# at32uc3a3256_usb_i2s.net
KiCad netlist of a schematic drawn in EAGLE
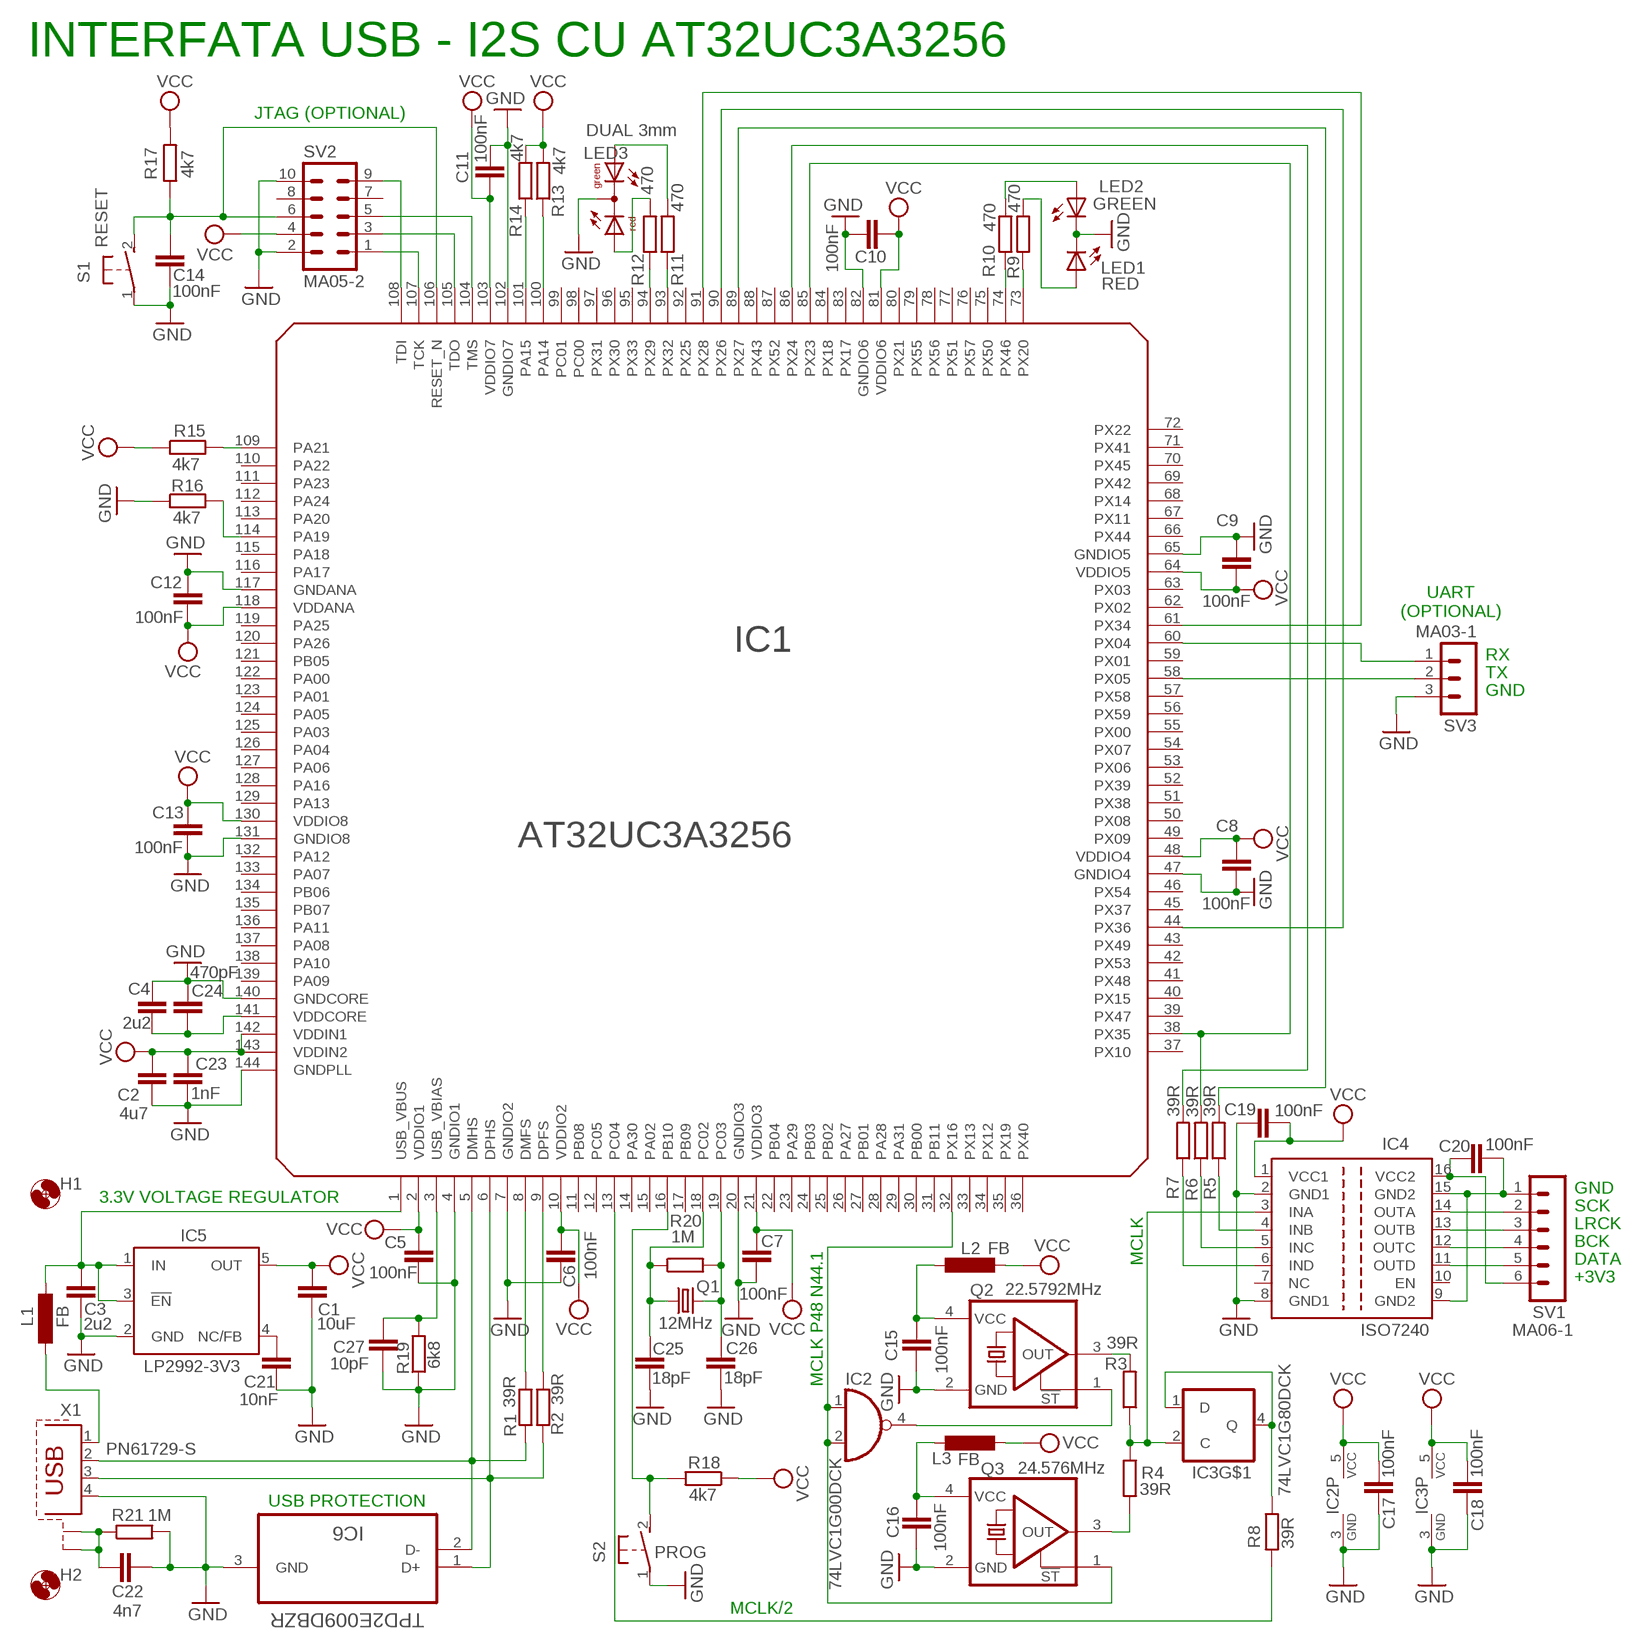
[diagram p0: schematic, sheet 1]

(export (version "E")
  (design (tool "Eeschema 10.0.6"))
  (components
    (comp (ref "C1")
      (value "10uF")
      (footprint "eagle-import:C0603")
      (libsource (lib "eagle-import") (part "C-EUC0603"))
    )
    (comp (ref "C2")
      (value "4u7")
      (footprint "eagle-import:C0603")
      (libsource (lib "eagle-import") (part "C-EUC0603"))
    )
    (comp (ref "C3")
      (value "2u2")
      (footprint "eagle-import:C0603")
      (libsource (lib "eagle-import") (part "C-EUC0603"))
    )
    (comp (ref "C4")
      (value "2u2")
      (footprint "eagle-import:C0603")
      (libsource (lib "eagle-import") (part "C-EUC0603"))
    )
    (comp (ref "C5")
      (value "100nF")
      (footprint "eagle-import:C0603")
      (libsource (lib "eagle-import") (part "C-EUC0603"))
    )
    (comp (ref "C6")
      (value "100nF")
      (footprint "eagle-import:C0603")
      (libsource (lib "eagle-import") (part "C-EUC0603"))
    )
    (comp (ref "C7")
      (value "100nF")
      (footprint "eagle-import:C0603")
      (libsource (lib "eagle-import") (part "C-EUC0603"))
    )
    (comp (ref "C8")
      (value "100nF")
      (footprint "eagle-import:C0603")
      (libsource (lib "eagle-import") (part "C-EUC0603"))
    )
    (comp (ref "C9")
      (value "100nF")
      (footprint "eagle-import:C0603")
      (libsource (lib "eagle-import") (part "C-EUC0603"))
    )
    (comp (ref "C10")
      (value "100nF")
      (footprint "eagle-import:C0603")
      (libsource (lib "eagle-import") (part "C-EUC0603"))
    )
    (comp (ref "C11")
      (value "100nF")
      (footprint "eagle-import:C0603")
      (libsource (lib "eagle-import") (part "C-EUC0603"))
    )
    (comp (ref "C12")
      (value "100nF")
      (footprint "eagle-import:C0603")
      (libsource (lib "eagle-import") (part "C-EUC0603"))
    )
    (comp (ref "C13")
      (value "100nF")
      (footprint "eagle-import:C0603")
      (libsource (lib "eagle-import") (part "C-EUC0603"))
    )
    (comp (ref "C14")
      (value "100nF")
      (footprint "eagle-import:C0603")
      (libsource (lib "eagle-import") (part "C-EUC0603"))
    )
    (comp (ref "C15")
      (value "100nF")
      (footprint "eagle-import:C0603")
      (libsource (lib "eagle-import") (part "C-EUC0603"))
    )
    (comp (ref "C16")
      (value "100nF")
      (footprint "eagle-import:C0603")
      (libsource (lib "eagle-import") (part "C-EUC0603"))
    )
    (comp (ref "C17")
      (value "100nF")
      (footprint "eagle-import:C0603")
      (libsource (lib "eagle-import") (part "C-EUC0603"))
    )
    (comp (ref "C18")
      (value "100nF")
      (footprint "eagle-import:C0603")
      (libsource (lib "eagle-import") (part "C-EUC0603"))
    )
    (comp (ref "C19")
      (value "100nF")
      (footprint "eagle-import:C0603")
      (libsource (lib "eagle-import") (part "C-EUC0603"))
    )
    (comp (ref "C20")
      (value "100nF")
      (footprint "eagle-import:C0603")
      (libsource (lib "eagle-import") (part "C-EUC0603"))
    )
    (comp (ref "C21")
      (value "10nF")
      (footprint "eagle-import:C0603")
      (libsource (lib "eagle-import") (part "C-EUC0603"))
    )
    (comp (ref "C22")
      (value "4n7")
      (footprint "eagle-import:C0603")
      (libsource (lib "eagle-import") (part "C-EUC0603"))
    )
    (comp (ref "C23")
      (value "1nF")
      (footprint "eagle-import:C0603")
      (libsource (lib "eagle-import") (part "C-EUC0603"))
    )
    (comp (ref "C24")
      (value "470pF")
      (footprint "eagle-import:C0603")
      (libsource (lib "eagle-import") (part "C-EUC0603"))
    )
    (comp (ref "C25")
      (value "18pF")
      (footprint "eagle-import:C0603")
      (libsource (lib "eagle-import") (part "C-EUC0603"))
    )
    (comp (ref "C26")
      (value "18pF")
      (footprint "eagle-import:C0603")
      (libsource (lib "eagle-import") (part "C-EUC0603"))
    )
    (comp (ref "C27")
      (value "10pF")
      (footprint "eagle-import:C0603")
      (libsource (lib "eagle-import") (part "C-EUC0603"))
    )
    (comp (ref "H1")
      (value "MOUNT-HOLE3.2")
      (footprint "eagle-import:3,2")
      (libsource (lib "eagle-import") (part "MOUNT-HOLE3.2"))
    )
    (comp (ref "H2")
      (value "MOUNT-HOLE3.2")
      (footprint "eagle-import:3,2")
      (libsource (lib "eagle-import") (part "MOUNT-HOLE3.2"))
    )
    (comp (ref "IC1")
      (value "AT32UC3A3256")
      (footprint "eagle-import:LQFP144")
      (libsource (lib "eagle-import") (part "AT32UC3A3256"))
    )
    (comp (ref "IC2")
      (value "74LVC1G00DCK")
      (footprint "eagle-import:SC70-5")
      (libsource (lib "eagle-import") (part "741G00DCKLVC"))
    )
    (comp (ref "IC3")
      (value "74LVC1G80DCK")
      (footprint "eagle-import:SC70-5")
      (libsource (lib "eagle-import") (part "741G79DCKLVC"))
    )
    (comp (ref "IC4")
      (value "ISO7240")
      (footprint "eagle-import:SO-16DW")
      (fields (field (name "MPN") "ISO7240MDW"))
      (libsource (lib "eagle-import") (part "ISO7240"))
    )
    (comp (ref "IC5")
      (value "LP2992-3V3")
      (footprint "eagle-import:SOT23-DBV")
      (fields (field (name "MF") "TEXAS INSTRUMENTS") (field (name "MPN") "TPS77001DBVT"))
      (libsource (lib "eagle-import") (part "TPS77001"))
    )
    (comp (ref "IC6")
      (value "TPD2E009DBZR")
      (footprint "eagle-import:SOT95P237X112-3N")
      (libsource (lib "eagle-import") (part "TPD2E009DBZR"))
    )
    (comp (ref "L1")
      (value "FB")
      (footprint "eagle-import:L2012C")
      (libsource (lib "eagle-import") (part "L-EUL2012C"))
    )
    (comp (ref "L2")
      (value "FB")
      (footprint "eagle-import:L2012C")
      (libsource (lib "eagle-import") (part "L-EUL2012C"))
    )
    (comp (ref "L3")
      (value "FB")
      (footprint "eagle-import:L2012C")
      (libsource (lib "eagle-import") (part "L-EUL2012C"))
    )
    (comp (ref "LED1")
      (value "RED")
      (footprint "eagle-import:CHIPLED_0603")
      (libsource (lib "eagle-import") (part "LEDCHIPLED_0603"))
    )
    (comp (ref "LED2")
      (value "GREEN")
      (footprint "eagle-import:CHIPLED_0603")
      (libsource (lib "eagle-import") (part "LEDCHIPLED_0603"))
    )
    (comp (ref "LED3")
      (value "DUAL 3mm")
      (footprint "eagle-import:DUOLED5MM")
      (libsource (lib "eagle-import") (part "DUOLED5MM"))
    )
    (comp (ref "Q1")
      (value "12MHz")
      (footprint "eagle-import:CTS406")
      (libsource (lib "eagle-import") (part "CRYSTALCTS406"))
    )
    (comp (ref "Q2")
      (value "22.5792MHz")
      (footprint "eagle-import:CRYSTAL2.5X2")
      (libsource (lib "eagle-import") (part "CRYSTAL2.5X2"))
    )
    (comp (ref "Q3")
      (value "24.576MHz")
      (footprint "eagle-import:CRYSTAL2.5X2")
      (libsource (lib "eagle-import") (part "CRYSTAL2.5X2"))
    )
    (comp (ref "R1")
      (value "39R")
      (footprint "eagle-import:R0603")
      (libsource (lib "eagle-import") (part "R-EU_R0603"))
    )
    (comp (ref "R2")
      (value "39R")
      (footprint "eagle-import:R0603")
      (libsource (lib "eagle-import") (part "R-EU_R0603"))
    )
    (comp (ref "R3")
      (value "39R")
      (footprint "eagle-import:R0603")
      (libsource (lib "eagle-import") (part "R-EU_R0603"))
    )
    (comp (ref "R4")
      (value "39R")
      (footprint "eagle-import:R0603")
      (libsource (lib "eagle-import") (part "R-EU_R0603"))
    )
    (comp (ref "R5")
      (value "39R")
      (footprint "eagle-import:R0603")
      (libsource (lib "eagle-import") (part "R-EU_R0603"))
    )
    (comp (ref "R6")
      (value "39R")
      (footprint "eagle-import:R0603")
      (libsource (lib "eagle-import") (part "R-EU_R0603"))
    )
    (comp (ref "R7")
      (value "39R")
      (footprint "eagle-import:R0603")
      (libsource (lib "eagle-import") (part "R-EU_R0603"))
    )
    (comp (ref "R8")
      (value "39R")
      (footprint "eagle-import:R0603")
      (libsource (lib "eagle-import") (part "R-EU_R0603"))
    )
    (comp (ref "R9")
      (value "470")
      (footprint "eagle-import:R0603")
      (libsource (lib "eagle-import") (part "R-EU_R0603"))
    )
    (comp (ref "R10")
      (value "470")
      (footprint "eagle-import:R0603")
      (libsource (lib "eagle-import") (part "R-EU_R0603"))
    )
    (comp (ref "R11")
      (value "470")
      (footprint "eagle-import:R0603")
      (libsource (lib "eagle-import") (part "R-EU_R0603"))
    )
    (comp (ref "R12")
      (value "470")
      (footprint "eagle-import:R0603")
      (libsource (lib "eagle-import") (part "R-EU_R0603"))
    )
    (comp (ref "R13")
      (value "4k7")
      (footprint "eagle-import:R0603")
      (libsource (lib "eagle-import") (part "R-EU_R0603"))
    )
    (comp (ref "R14")
      (value "4k7")
      (footprint "eagle-import:R0603")
      (libsource (lib "eagle-import") (part "R-EU_R0603"))
    )
    (comp (ref "R15")
      (value "4k7")
      (footprint "eagle-import:R0603")
      (libsource (lib "eagle-import") (part "R-EU_R0603"))
    )
    (comp (ref "R16")
      (value "4k7")
      (footprint "eagle-import:R0603")
      (libsource (lib "eagle-import") (part "R-EU_R0603"))
    )
    (comp (ref "R17")
      (value "4k7")
      (footprint "eagle-import:R0603")
      (libsource (lib "eagle-import") (part "R-EU_R0603"))
    )
    (comp (ref "R18")
      (value "4k7")
      (footprint "eagle-import:R0603")
      (libsource (lib "eagle-import") (part "R-EU_R0603"))
    )
    (comp (ref "R19")
      (value "6k8")
      (footprint "eagle-import:R0603")
      (libsource (lib "eagle-import") (part "R-EU_R0603"))
    )
    (comp (ref "R20")
      (value "1M")
      (footprint "eagle-import:R0603")
      (libsource (lib "eagle-import") (part "R-EU_R0603"))
    )
    (comp (ref "R21")
      (value "1M")
      (footprint "eagle-import:R0603")
      (libsource (lib "eagle-import") (part "R-EU_R0603"))
    )
    (comp (ref "S1")
      (value "RESET")
      (footprint "eagle-import:SWITCH-KSR")
      (libsource (lib "eagle-import") (part "SWITCH-KSR"))
    )
    (comp (ref "S2")
      (value "PROG")
      (footprint "eagle-import:SWITCH-KSR")
      (libsource (lib "eagle-import") (part "SWITCH-KSR"))
    )
    (comp (ref "SV1")
      (value "MA06-1")
      (footprint "eagle-import:MA06-1")
      (libsource (lib "eagle-import") (part "MA06-1"))
    )
    (comp (ref "SV2")
      (value "MA05-2")
      (footprint "eagle-import:MA05-2")
      (libsource (lib "eagle-import") (part "MA05-2"))
    )
    (comp (ref "SV3")
      (value "MA03-1")
      (footprint "eagle-import:MA03-1")
      (libsource (lib "eagle-import") (part "MA03-1"))
    )
    (comp (ref "X1")
      (value "PN61729-S")
      (footprint "eagle-import:PN61729-S")
      (libsource (lib "eagle-import") (part "PN61729-S"))
    )
  )
  (nets
    (net (code "1") (name "GND") (class "Default")
      (node (ref "C1") (pin "2") (pinfunction "2_2") (pintype "passive"))
      (node (ref "C10") (pin "1") (pinfunction "1_1") (pintype "passive"))
      (node (ref "C11") (pin "1") (pinfunction "1_1") (pintype "passive"))
      (node (ref "C12") (pin "1") (pinfunction "1_1") (pintype "passive"))
      (node (ref "C13") (pin "1") (pinfunction "1_1") (pintype "passive"))
      (node (ref "C14") (pin "2") (pinfunction "2_2") (pintype "passive"))
      (node (ref "C15") (pin "1") (pinfunction "1_1") (pintype "passive"))
      (node (ref "C16") (pin "1") (pinfunction "1_1") (pintype "passive"))
      (node (ref "C17") (pin "2") (pinfunction "2_2") (pintype "passive"))
      (node (ref "C18") (pin "2") (pinfunction "2_2") (pintype "passive"))
      (node (ref "C19") (pin "1") (pinfunction "1_1") (pintype "passive"))
      (node (ref "C2") (pin "2") (pinfunction "2_2") (pintype "passive"))
      (node (ref "C21") (pin "2") (pinfunction "2_2") (pintype "passive"))
      (node (ref "C22") (pin "2") (pinfunction "2_2") (pintype "passive"))
      (node (ref "C23") (pin "2") (pinfunction "2_2") (pintype "passive"))
      (node (ref "C24") (pin "1") (pinfunction "1_1") (pintype "passive"))
      (node (ref "C25") (pin "2") (pinfunction "2_2") (pintype "passive"))
      (node (ref "C26") (pin "2") (pinfunction "2_2") (pintype "passive"))
      (node (ref "C27") (pin "2") (pinfunction "2_2") (pintype "passive"))
      (node (ref "C3") (pin "2") (pinfunction "2_2") (pintype "passive"))
      (node (ref "C4") (pin "1") (pinfunction "1_1") (pintype "passive"))
      (node (ref "C5") (pin "2") (pinfunction "2_2") (pintype "passive"))
      (node (ref "C6") (pin "2") (pinfunction "2_2") (pintype "passive"))
      (node (ref "C7") (pin "2") (pinfunction "2_2") (pintype "passive"))
      (node (ref "C8") (pin "2") (pinfunction "2_2") (pintype "passive"))
      (node (ref "C9") (pin "1") (pinfunction "1_1") (pintype "passive"))
      (node (ref "IC1") (pin "102") (pinfunction "GNDIO7_102") (pintype "bidirectional"))
      (node (ref "IC1") (pin "117") (pinfunction "GNDANA_117") (pintype "bidirectional"))
      (node (ref "IC1") (pin "131") (pinfunction "GNDIO8_131") (pintype "bidirectional"))
      (node (ref "IC1") (pin "140") (pinfunction "GNDCORE_140") (pintype "bidirectional"))
      (node (ref "IC1") (pin "144") (pinfunction "GNDPLL_144") (pintype "bidirectional"))
      (node (ref "IC1") (pin "20") (pinfunction "GNDIO3_20") (pintype "bidirectional"))
      (node (ref "IC1") (pin "4") (pinfunction "GNDIO1_4") (pintype "bidirectional"))
      (node (ref "IC1") (pin "47") (pinfunction "GNDIO4_47") (pintype "bidirectional"))
      (node (ref "IC1") (pin "65") (pinfunction "GNDIO5_65") (pintype "bidirectional"))
      (node (ref "IC1") (pin "7") (pinfunction "GNDIO2_7") (pintype "bidirectional"))
      (node (ref "IC1") (pin "82") (pinfunction "GNDIO6_82") (pintype "bidirectional"))
      (node (ref "IC2") (pin "3") (pinfunction "GND_3") (pintype "power_in"))
      (node (ref "IC3") (pin "3") (pinfunction "GND_3") (pintype "power_in"))
      (node (ref "IC4") (pin "2") (pinfunction "GND1_2") (pintype "power_in"))
      (node (ref "IC4") (pin "8") (pinfunction "GND1_8") (pintype "power_in"))
      (node (ref "IC5") (pin "2") (pinfunction "GND_2") (pintype "power_in"))
      (node (ref "IC6") (pin "3") (pinfunction "GND_3") (pintype "passive"))
      (node (ref "LED1") (pin "C") (pinfunction "C_C") (pintype "passive"))
      (node (ref "LED2") (pin "C") (pinfunction "C_C") (pintype "passive"))
      (node (ref "LED3") (pin "K") (pinfunction "C_K") (pintype "passive"))
      (node (ref "Q2") (pin "2") (pinfunction "GND_2") (pintype "power_in"))
      (node (ref "Q3") (pin "2") (pinfunction "GND_2") (pintype "power_in"))
      (node (ref "R16") (pin "1") (pinfunction "1_1") (pintype "passive"))
      (node (ref "R19") (pin "1") (pinfunction "1_1") (pintype "passive"))
      (node (ref "R21") (pin "2") (pinfunction "2_2") (pintype "passive"))
      (node (ref "S1") (pin "1") (pinfunction "1_1") (pintype "passive"))
      (node (ref "S2") (pin "1") (pinfunction "1_1") (pintype "passive"))
      (node (ref "SV2") (pin "10") (pinfunction "10_10") (pintype "passive"))
      (node (ref "SV2") (pin "2") (pinfunction "2_2") (pintype "passive"))
      (node (ref "SV3") (pin "3") (pinfunction "3_3") (pintype "passive"))
      (node (ref "X1") (pin "4") (pinfunction "4_4") (pintype "passive"))
    )
    (net (code "2") (name "Net-(C20-Pad2)") (class "Default")
      (node (ref "C20") (pin "2") (pinfunction "2_2") (pintype "passive"))
      (node (ref "IC4") (pin "15") (pinfunction "GND2_15") (pintype "power_in"))
      (node (ref "IC4") (pin "9") (pinfunction "GND2_9") (pintype "power_in"))
      (node (ref "SV1") (pin "1") (pinfunction "1_1") (pintype "passive"))
    )
    (net (code "3") (name "Net-(C22-Pad1)") (class "Default")
      (node (ref "C22") (pin "1") (pinfunction "1_1") (pintype "passive"))
      (node (ref "R21") (pin "1") (pinfunction "1_1") (pintype "passive"))
      (node (ref "X1") (pin "S1") (pinfunction "S1_S1") (pintype "passive"))
      (node (ref "X1") (pin "S2") (pinfunction "S2_S2") (pintype "passive"))
    )
    (net (code "4") (name "Net-(IC1-DMFS)") (class "Default")
      (node (ref "IC1") (pin "8") (pinfunction "DMFS_8") (pintype "bidirectional"))
      (node (ref "R1") (pin "2") (pinfunction "2_2") (pintype "passive"))
    )
    (net (code "5") (name "Net-(IC1-DMHS)") (class "Default")
      (node (ref "IC1") (pin "5") (pinfunction "DMHS_5") (pintype "bidirectional"))
      (node (ref "IC6") (pin "2") (pinfunction "D-_2") (pintype "passive"))
      (node (ref "R1") (pin "1") (pinfunction "1_1") (pintype "passive"))
      (node (ref "X1") (pin "2") (pinfunction "2_2") (pintype "passive"))
    )
    (net (code "6") (name "Net-(IC1-DPFS)") (class "Default")
      (node (ref "IC1") (pin "9") (pinfunction "DPFS_9") (pintype "bidirectional"))
      (node (ref "R2") (pin "2") (pinfunction "2_2") (pintype "passive"))
    )
    (net (code "7") (name "Net-(IC1-DPHS)") (class "Default")
      (node (ref "IC1") (pin "6") (pinfunction "DPHS_6") (pintype "bidirectional"))
      (node (ref "IC6") (pin "1") (pinfunction "D+_1") (pintype "passive"))
      (node (ref "R2") (pin "1") (pinfunction "1_1") (pintype "passive"))
      (node (ref "X1") (pin "3") (pinfunction "3_3") (pintype "passive"))
    )
    (net (code "8") (name "Net-(IC1-PA14)") (class "Default")
      (node (ref "IC1") (pin "100") (pinfunction "PA14_100") (pintype "bidirectional"))
      (node (ref "R13") (pin "1") (pinfunction "1_1") (pintype "passive"))
    )
    (net (code "9") (name "Net-(IC1-PA15)") (class "Default")
      (node (ref "IC1") (pin "101") (pinfunction "PA15_101") (pintype "bidirectional"))
      (node (ref "R14") (pin "1") (pinfunction "1_1") (pintype "passive"))
    )
    (net (code "10") (name "Net-(IC1-PA19)") (class "Default")
      (node (ref "IC1") (pin "114") (pinfunction "PA19_114") (pintype "bidirectional"))
      (node (ref "R16") (pin "2") (pinfunction "2_2") (pintype "passive"))
    )
    (net (code "11") (name "Net-(IC1-PA21)") (class "Default")
      (node (ref "IC1") (pin "109") (pinfunction "PA21_109") (pintype "bidirectional"))
      (node (ref "R15") (pin "2") (pinfunction "2_2") (pintype "passive"))
    )
    (net (code "12") (name "Net-(IC1-PB10)") (class "Default")
      (node (ref "IC1") (pin "16") (pinfunction "PB10_16") (pintype "bidirectional"))
      (node (ref "R18") (pin "2") (pinfunction "2_2") (pintype "passive"))
      (node (ref "S2") (pin "2") (pinfunction "2_2") (pintype "passive"))
    )
    (net (code "13") (name "Net-(IC1-PC02)") (class "Default")
      (node (ref "C25") (pin "1") (pinfunction "1_1") (pintype "passive"))
      (node (ref "IC1") (pin "18") (pinfunction "PC02_18") (pintype "bidirectional"))
      (node (ref "Q1") (pin "1") (pinfunction "1_1") (pintype "passive"))
      (node (ref "R20") (pin "1") (pinfunction "1_1") (pintype "passive"))
    )
    (net (code "14") (name "Net-(IC1-PC03)") (class "Default")
      (node (ref "C26") (pin "1") (pinfunction "1_1") (pintype "passive"))
      (node (ref "IC1") (pin "19") (pinfunction "PC03_19") (pintype "bidirectional"))
      (node (ref "Q1") (pin "3") (pinfunction "2_3") (pintype "passive"))
      (node (ref "R20") (pin "2") (pinfunction "2_2") (pintype "passive"))
    )
    (net (code "15") (name "Net-(IC1-PC04)") (class "Default")
      (node (ref "IC1") (pin "13") (pinfunction "PC04_13") (pintype "bidirectional"))
      (node (ref "R8") (pin "1") (pinfunction "1_1") (pintype "passive"))
    )
    (net (code "16") (name "Net-(IC1-PX04)") (class "Default")
      (node (ref "IC1") (pin "60") (pinfunction "PX04_60") (pintype "bidirectional"))
      (node (ref "SV3") (pin "1") (pinfunction "1_1") (pintype "passive"))
    )
    (net (code "17") (name "Net-(IC1-PX05)") (class "Default")
      (node (ref "IC1") (pin "58") (pinfunction "PX05_58") (pintype "bidirectional"))
      (node (ref "SV3") (pin "2") (pinfunction "2_2") (pintype "passive"))
    )
    (net (code "18") (name "Net-(IC1-PX16)") (class "Default")
      (node (ref "IC1") (pin "32") (pinfunction "PX16_32") (pintype "bidirectional"))
      (node (ref "IC2") (pin "1") (pinfunction "I0_1") (pintype "input"))
      (node (ref "IC2") (pin "2") (pinfunction "I1_2") (pintype "input"))
      (node (ref "Q3") (pin "1") (pinfunction "~{ST}_1") (pintype "input"))
    )
    (net (code "19") (name "Net-(IC1-PX20)") (class "Default")
      (node (ref "IC1") (pin "73") (pinfunction "PX20_73") (pintype "bidirectional"))
      (node (ref "R9") (pin "1") (pinfunction "1_1") (pintype "passive"))
    )
    (net (code "20") (name "Net-(IC1-PX23)") (class "Default")
      (node (ref "IC1") (pin "38") (pinfunction "PX35_38") (pintype "bidirectional"))
      (node (ref "IC1") (pin "85") (pinfunction "PX23_85") (pintype "bidirectional"))
      (node (ref "R6") (pin "2") (pinfunction "2_2") (pintype "passive"))
    )
    (net (code "21") (name "Net-(IC1-PX24)") (class "Default")
      (node (ref "IC1") (pin "86") (pinfunction "PX24_86") (pintype "bidirectional"))
      (node (ref "R7") (pin "2") (pinfunction "2_2") (pintype "passive"))
    )
    (net (code "22") (name "Net-(IC1-PX26)") (class "Default")
      (node (ref "IC1") (pin "44") (pinfunction "PX36_44") (pintype "bidirectional"))
      (node (ref "IC1") (pin "90") (pinfunction "PX26_90") (pintype "bidirectional"))
    )
    (net (code "23") (name "Net-(IC1-PX27)") (class "Default")
      (node (ref "IC1") (pin "89") (pinfunction "PX27_89") (pintype "bidirectional"))
      (node (ref "R5") (pin "2") (pinfunction "2_2") (pintype "passive"))
    )
    (net (code "24") (name "Net-(IC1-PX28)") (class "Default")
      (node (ref "IC1") (pin "61") (pinfunction "PX34_61") (pintype "bidirectional"))
      (node (ref "IC1") (pin "91") (pinfunction "PX28_91") (pintype "bidirectional"))
    )
    (net (code "25") (name "Net-(IC1-PX29)") (class "Default")
      (node (ref "IC1") (pin "94") (pinfunction "PX29_94") (pintype "bidirectional"))
      (node (ref "R12") (pin "1") (pinfunction "1_1") (pintype "passive"))
    )
    (net (code "26") (name "Net-(IC1-PX32)") (class "Default")
      (node (ref "IC1") (pin "93") (pinfunction "PX32_93") (pintype "bidirectional"))
      (node (ref "R11") (pin "1") (pinfunction "1_1") (pintype "passive"))
    )
    (net (code "27") (name "Net-(IC1-PX46)") (class "Default")
      (node (ref "IC1") (pin "74") (pinfunction "PX46_74") (pintype "bidirectional"))
      (node (ref "R10") (pin "1") (pinfunction "1_1") (pintype "passive"))
    )
    (net (code "28") (name "Net-(IC1-RESET_N)") (class "Default")
      (node (ref "C14") (pin "1") (pinfunction "1_1") (pintype "passive"))
      (node (ref "IC1") (pin "106") (pinfunction "RESET_N_106") (pintype "bidirectional"))
      (node (ref "R17") (pin "1") (pinfunction "1_1") (pintype "passive"))
      (node (ref "S1") (pin "2") (pinfunction "2_2") (pintype "passive"))
      (node (ref "SV2") (pin "6") (pinfunction "6_6") (pintype "passive"))
    )
    (net (code "29") (name "Net-(IC1-TCK)") (class "Default")
      (node (ref "IC1") (pin "107") (pinfunction "TCK_107") (pintype "bidirectional"))
      (node (ref "SV2") (pin "1") (pinfunction "1_1") (pintype "passive"))
    )
    (net (code "30") (name "Net-(IC1-TDI)") (class "Default")
      (node (ref "IC1") (pin "108") (pinfunction "TDI_108") (pintype "bidirectional"))
      (node (ref "SV2") (pin "9") (pinfunction "9_9") (pintype "passive"))
    )
    (net (code "31") (name "Net-(IC1-TDO)") (class "Default")
      (node (ref "IC1") (pin "105") (pinfunction "TDO_105") (pintype "bidirectional"))
      (node (ref "SV2") (pin "3") (pinfunction "3_3") (pintype "passive"))
    )
    (net (code "32") (name "Net-(IC1-TMS)") (class "Default")
      (node (ref "IC1") (pin "104") (pinfunction "TMS_104") (pintype "bidirectional"))
      (node (ref "SV2") (pin "5") (pinfunction "5_5") (pintype "passive"))
    )
    (net (code "33") (name "Net-(IC1-USB_VBIAS)") (class "Default")
      (node (ref "C27") (pin "1") (pinfunction "1_1") (pintype "passive"))
      (node (ref "IC1") (pin "3") (pinfunction "USB_VBIAS_3") (pintype "bidirectional"))
      (node (ref "R19") (pin "2") (pinfunction "2_2") (pintype "passive"))
    )
    (net (code "34") (name "Net-(IC1-USB_VBUS)") (class "Default")
      (node (ref "C3") (pin "1") (pinfunction "1_1") (pintype "passive"))
      (node (ref "IC1") (pin "1") (pinfunction "USB_VBUS_1") (pintype "bidirectional"))
      (node (ref "IC5") (pin "1") (pinfunction "IN_1") (pintype "input"))
      (node (ref "IC5") (pin "3") (pinfunction "~{EN}_3") (pintype "input"))
      (node (ref "L1") (pin "2") (pinfunction "2_2") (pintype "passive"))
    )
    (net (code "35") (name "Net-(IC1-VDDCORE)") (class "Default")
      (node (ref "C24") (pin "2") (pinfunction "2_2") (pintype "passive"))
      (node (ref "C4") (pin "2") (pinfunction "2_2") (pintype "passive"))
      (node (ref "IC1") (pin "141") (pinfunction "VDDCORE_141") (pintype "bidirectional"))
    )
    (net (code "36") (name "Net-(IC2A-O)") (class "Default")
      (node (ref "IC2") (pin "4") (pinfunction "O_4") (pintype "output"))
      (node (ref "Q2") (pin "1") (pinfunction "~{ST}_1") (pintype "input"))
    )
    (net (code "37") (name "Net-(IC3A-C)") (class "Default")
      (node (ref "IC3") (pin "2") (pinfunction "C_2") (pintype "input"))
      (node (ref "IC4") (pin "3") (pinfunction "INA_3") (pintype "input"))
      (node (ref "R3") (pin "1") (pinfunction "1_1") (pintype "passive"))
      (node (ref "R4") (pin "2") (pinfunction "2_2") (pintype "passive"))
    )
    (net (code "38") (name "Net-(IC3A-D)") (class "Default")
      (node (ref "IC3") (pin "1") (pinfunction "D_1") (pintype "input"))
      (node (ref "IC3") (pin "4") (pinfunction "Q_4") (pintype "output"))
      (node (ref "R8") (pin "2") (pinfunction "2_2") (pintype "passive"))
    )
    (net (code "39") (name "Net-(IC4-INB)") (class "Default")
      (node (ref "IC4") (pin "4") (pinfunction "INB_4") (pintype "input"))
      (node (ref "R5") (pin "1") (pinfunction "1_1") (pintype "passive"))
    )
    (net (code "40") (name "Net-(IC4-INC)") (class "Default")
      (node (ref "IC4") (pin "5") (pinfunction "INC_5") (pintype "input"))
      (node (ref "R6") (pin "1") (pinfunction "1_1") (pintype "passive"))
    )
    (net (code "41") (name "Net-(IC4-IND)") (class "Default")
      (node (ref "IC4") (pin "6") (pinfunction "IND_6") (pintype "input"))
      (node (ref "R7") (pin "1") (pinfunction "1_1") (pintype "passive"))
    )
    (net (code "42") (name "Net-(IC4-OUTA)") (class "Default")
      (node (ref "IC4") (pin "14") (pinfunction "OUTA_14") (pintype "output"))
      (node (ref "SV1") (pin "2") (pinfunction "2_2") (pintype "passive"))
    )
    (net (code "43") (name "Net-(IC4-OUTB)") (class "Default")
      (node (ref "IC4") (pin "13") (pinfunction "OUTB_13") (pintype "output"))
      (node (ref "SV1") (pin "3") (pinfunction "3_3") (pintype "passive"))
    )
    (net (code "44") (name "Net-(IC4-OUTC)") (class "Default")
      (node (ref "IC4") (pin "12") (pinfunction "OUTC_12") (pintype "output"))
      (node (ref "SV1") (pin "4") (pinfunction "4_4") (pintype "passive"))
    )
    (net (code "45") (name "Net-(IC4-OUTD)") (class "Default")
      (node (ref "IC4") (pin "11") (pinfunction "OUTD_11") (pintype "output"))
      (node (ref "SV1") (pin "5") (pinfunction "5_5") (pintype "passive"))
    )
    (net (code "46") (name "Net-(IC4-VCC2)") (class "Default")
      (node (ref "C20") (pin "1") (pinfunction "1_1") (pintype "passive"))
      (node (ref "IC4") (pin "16") (pinfunction "VCC2_16") (pintype "power_in"))
      (node (ref "SV1") (pin "6") (pinfunction "6_6") (pintype "passive"))
    )
    (net (code "47") (name "Net-(IC5-NC{slash}FB)") (class "Default")
      (node (ref "C21") (pin "1") (pinfunction "1_1") (pintype "passive"))
      (node (ref "IC5") (pin "4") (pinfunction "NC/FB_4") (pintype "passive"))
    )
    (net (code "48") (name "Net-(L1-Pad1)") (class "Default")
      (node (ref "L1") (pin "1") (pinfunction "1_1") (pintype "passive"))
      (node (ref "X1") (pin "1") (pinfunction "1_1") (pintype "passive"))
    )
    (net (code "49") (name "Net-(LED1-PadA)") (class "Default")
      (node (ref "LED1") (pin "A") (pinfunction "A_A") (pintype "passive"))
      (node (ref "R9") (pin "2") (pinfunction "2_2") (pintype "passive"))
    )
    (net (code "50") (name "Net-(LED2-PadA)") (class "Default")
      (node (ref "LED2") (pin "A") (pinfunction "A_A") (pintype "passive"))
      (node (ref "R10") (pin "2") (pinfunction "2_2") (pintype "passive"))
    )
    (net (code "51") (name "Net-(LED3-PadAG)") (class "Default")
      (node (ref "LED3") (pin "AG") (pinfunction "AG_AG") (pintype "passive"))
      (node (ref "R11") (pin "2") (pinfunction "2_2") (pintype "passive"))
    )
    (net (code "52") (name "Net-(LED3-PadAR)") (class "Default")
      (node (ref "LED3") (pin "AR") (pinfunction "AR_AR") (pintype "passive"))
      (node (ref "R12") (pin "2") (pinfunction "2_2") (pintype "passive"))
    )
    (net (code "53") (name "Net-(Q2-OUT)") (class "Default")
      (node (ref "Q2") (pin "3") (pinfunction "OUT_3") (pintype "output"))
      (node (ref "R3") (pin "2") (pinfunction "2_2") (pintype "passive"))
    )
    (net (code "54") (name "Net-(Q2-VCC)") (class "Default")
      (node (ref "C15") (pin "2") (pinfunction "2_2") (pintype "passive"))
      (node (ref "L2") (pin "2") (pinfunction "2_2") (pintype "passive"))
      (node (ref "Q2") (pin "4") (pinfunction "VCC_4") (pintype "power_in"))
    )
    (net (code "55") (name "Net-(Q3-OUT)") (class "Default")
      (node (ref "Q3") (pin "3") (pinfunction "OUT_3") (pintype "output"))
      (node (ref "R4") (pin "1") (pinfunction "1_1") (pintype "passive"))
    )
    (net (code "56") (name "Net-(Q3-VCC)") (class "Default")
      (node (ref "C16") (pin "2") (pinfunction "2_2") (pintype "passive"))
      (node (ref "L3") (pin "2") (pinfunction "2_2") (pintype "passive"))
      (node (ref "Q3") (pin "4") (pinfunction "VCC_4") (pintype "power_in"))
    )
    (net (code "57") (name "VCC") (class "Default")
      (node (ref "C1") (pin "1") (pinfunction "1_1") (pintype "passive"))
      (node (ref "C10") (pin "2") (pinfunction "2_2") (pintype "passive"))
      (node (ref "C11") (pin "2") (pinfunction "2_2") (pintype "passive"))
      (node (ref "C12") (pin "2") (pinfunction "2_2") (pintype "passive"))
      (node (ref "C13") (pin "2") (pinfunction "2_2") (pintype "passive"))
      (node (ref "C17") (pin "1") (pinfunction "1_1") (pintype "passive"))
      (node (ref "C18") (pin "1") (pinfunction "1_1") (pintype "passive"))
      (node (ref "C19") (pin "2") (pinfunction "2_2") (pintype "passive"))
      (node (ref "C2") (pin "1") (pinfunction "1_1") (pintype "passive"))
      (node (ref "C23") (pin "1") (pinfunction "1_1") (pintype "passive"))
      (node (ref "C5") (pin "1") (pinfunction "1_1") (pintype "passive"))
      (node (ref "C6") (pin "1") (pinfunction "1_1") (pintype "passive"))
      (node (ref "C7") (pin "1") (pinfunction "1_1") (pintype "passive"))
      (node (ref "C8") (pin "1") (pinfunction "1_1") (pintype "passive"))
      (node (ref "C9") (pin "2") (pinfunction "2_2") (pintype "passive"))
      (node (ref "IC1") (pin "10") (pinfunction "VDDIO2_10") (pintype "bidirectional"))
      (node (ref "IC1") (pin "103") (pinfunction "VDDIO7_103") (pintype "bidirectional"))
      (node (ref "IC1") (pin "118") (pinfunction "VDDANA_118") (pintype "bidirectional"))
      (node (ref "IC1") (pin "130") (pinfunction "VDDIO8_130") (pintype "bidirectional"))
      (node (ref "IC1") (pin "142") (pinfunction "VDDIN1_142") (pintype "bidirectional"))
      (node (ref "IC1") (pin "143") (pinfunction "VDDIN2_143") (pintype "bidirectional"))
      (node (ref "IC1") (pin "2") (pinfunction "VDDIO1_2") (pintype "bidirectional"))
      (node (ref "IC1") (pin "21") (pinfunction "VDDIO3_21") (pintype "bidirectional"))
      (node (ref "IC1") (pin "48") (pinfunction "VDDIO4_48") (pintype "bidirectional"))
      (node (ref "IC1") (pin "64") (pinfunction "VDDIO5_64") (pintype "bidirectional"))
      (node (ref "IC1") (pin "81") (pinfunction "VDDIO6_81") (pintype "bidirectional"))
      (node (ref "IC2") (pin "5") (pinfunction "VCC_5") (pintype "power_in"))
      (node (ref "IC3") (pin "5") (pinfunction "VCC_5") (pintype "power_in"))
      (node (ref "IC4") (pin "1") (pinfunction "VCC1_1") (pintype "power_in"))
      (node (ref "IC5") (pin "5") (pinfunction "OUT_5") (pintype "passive"))
      (node (ref "L2") (pin "1") (pinfunction "1_1") (pintype "passive"))
      (node (ref "L3") (pin "1") (pinfunction "1_1") (pintype "passive"))
      (node (ref "R13") (pin "2") (pinfunction "2_2") (pintype "passive"))
      (node (ref "R14") (pin "2") (pinfunction "2_2") (pintype "passive"))
      (node (ref "R15") (pin "1") (pinfunction "1_1") (pintype "passive"))
      (node (ref "R17") (pin "2") (pinfunction "2_2") (pintype "passive"))
      (node (ref "R18") (pin "1") (pinfunction "1_1") (pintype "passive"))
      (node (ref "SV2") (pin "4") (pinfunction "4_4") (pintype "passive"))
    )
    (net (code "58") (name "unconnected-(IC1-PA00-Pad122)") (class "Default")
      (node (ref "IC1") (pin "122") (pinfunction "PA00_122") (pintype "bidirectional"))
    )
    (net (code "59") (name "unconnected-(IC1-PA01-Pad123)") (class "Default")
      (node (ref "IC1") (pin "123") (pinfunction "PA01_123") (pintype "bidirectional"))
    )
    (net (code "60") (name "unconnected-(IC1-PA02-Pad15)") (class "Default")
      (node (ref "IC1") (pin "15") (pinfunction "PA02_15") (pintype "bidirectional"))
    )
    (net (code "61") (name "unconnected-(IC1-PA03-Pad125)") (class "Default")
      (node (ref "IC1") (pin "125") (pinfunction "PA03_125") (pintype "bidirectional"))
    )
    (net (code "62") (name "unconnected-(IC1-PA04-Pad126)") (class "Default")
      (node (ref "IC1") (pin "126") (pinfunction "PA04_126") (pintype "bidirectional"))
    )
    (net (code "63") (name "unconnected-(IC1-PA05-Pad124)") (class "Default")
      (node (ref "IC1") (pin "124") (pinfunction "PA05_124") (pintype "bidirectional"))
    )
    (net (code "64") (name "unconnected-(IC1-PA06-Pad127)") (class "Default")
      (node (ref "IC1") (pin "127") (pinfunction "PA06_127") (pintype "bidirectional"))
    )
    (net (code "65") (name "unconnected-(IC1-PA07-Pad133)") (class "Default")
      (node (ref "IC1") (pin "133") (pinfunction "PA07_133") (pintype "bidirectional"))
    )
    (net (code "66") (name "unconnected-(IC1-PA08-Pad137)") (class "Default")
      (node (ref "IC1") (pin "137") (pinfunction "PA08_137") (pintype "bidirectional"))
    )
    (net (code "67") (name "unconnected-(IC1-PA09-Pad139)") (class "Default")
      (node (ref "IC1") (pin "139") (pinfunction "PA09_139") (pintype "bidirectional"))
    )
    (net (code "68") (name "unconnected-(IC1-PA10-Pad138)") (class "Default")
      (node (ref "IC1") (pin "138") (pinfunction "PA10_138") (pintype "bidirectional"))
    )
    (net (code "69") (name "unconnected-(IC1-PA11-Pad136)") (class "Default")
      (node (ref "IC1") (pin "136") (pinfunction "PA11_136") (pintype "bidirectional"))
    )
    (net (code "70") (name "unconnected-(IC1-PA12-Pad132)") (class "Default")
      (node (ref "IC1") (pin "132") (pinfunction "PA12_132") (pintype "bidirectional"))
    )
    (net (code "71") (name "unconnected-(IC1-PA13-Pad129)") (class "Default")
      (node (ref "IC1") (pin "129") (pinfunction "PA13_129") (pintype "bidirectional"))
    )
    (net (code "72") (name "unconnected-(IC1-PA16-Pad128)") (class "Default")
      (node (ref "IC1") (pin "128") (pinfunction "PA16_128") (pintype "bidirectional"))
    )
    (net (code "73") (name "unconnected-(IC1-PA17-Pad116)") (class "Default")
      (node (ref "IC1") (pin "116") (pinfunction "PA17_116") (pintype "bidirectional"))
    )
    (net (code "74") (name "unconnected-(IC1-PA18-Pad115)") (class "Default")
      (node (ref "IC1") (pin "115") (pinfunction "PA18_115") (pintype "bidirectional"))
    )
    (net (code "75") (name "unconnected-(IC1-PA20-Pad113)") (class "Default")
      (node (ref "IC1") (pin "113") (pinfunction "PA20_113") (pintype "bidirectional"))
    )
    (net (code "76") (name "unconnected-(IC1-PA22-Pad110)") (class "Default")
      (node (ref "IC1") (pin "110") (pinfunction "PA22_110") (pintype "bidirectional"))
    )
    (net (code "77") (name "unconnected-(IC1-PA23-Pad111)") (class "Default")
      (node (ref "IC1") (pin "111") (pinfunction "PA23_111") (pintype "bidirectional"))
    )
    (net (code "78") (name "unconnected-(IC1-PA24-Pad112)") (class "Default")
      (node (ref "IC1") (pin "112") (pinfunction "PA24_112") (pintype "bidirectional"))
    )
    (net (code "79") (name "unconnected-(IC1-PA25-Pad119)") (class "Default")
      (node (ref "IC1") (pin "119") (pinfunction "PA25_119") (pintype "bidirectional"))
    )
    (net (code "80") (name "unconnected-(IC1-PA26-Pad120)") (class "Default")
      (node (ref "IC1") (pin "120") (pinfunction "PA26_120") (pintype "bidirectional"))
    )
    (net (code "81") (name "unconnected-(IC1-PA27-Pad26)") (class "Default")
      (node (ref "IC1") (pin "26") (pinfunction "PA27_26") (pintype "bidirectional"))
    )
    (net (code "82") (name "unconnected-(IC1-PA28-Pad28)") (class "Default")
      (node (ref "IC1") (pin "28") (pinfunction "PA28_28") (pintype "bidirectional"))
    )
    (net (code "83") (name "unconnected-(IC1-PA29-Pad23)") (class "Default")
      (node (ref "IC1") (pin "23") (pinfunction "PA29_23") (pintype "bidirectional"))
    )
    (net (code "84") (name "unconnected-(IC1-PA30-Pad14)") (class "Default")
      (node (ref "IC1") (pin "14") (pinfunction "PA30_14") (pintype "bidirectional"))
    )
    (net (code "85") (name "unconnected-(IC1-PA31-Pad29)") (class "Default")
      (node (ref "IC1") (pin "29") (pinfunction "PA31_29") (pintype "bidirectional"))
    )
    (net (code "86") (name "unconnected-(IC1-PB00-Pad30)") (class "Default")
      (node (ref "IC1") (pin "30") (pinfunction "PB00_30") (pintype "bidirectional"))
    )
    (net (code "87") (name "unconnected-(IC1-PB01-Pad27)") (class "Default")
      (node (ref "IC1") (pin "27") (pinfunction "PB01_27") (pintype "bidirectional"))
    )
    (net (code "88") (name "unconnected-(IC1-PB02-Pad25)") (class "Default")
      (node (ref "IC1") (pin "25") (pinfunction "PB02_25") (pintype "bidirectional"))
    )
    (net (code "89") (name "unconnected-(IC1-PB03-Pad24)") (class "Default")
      (node (ref "IC1") (pin "24") (pinfunction "PB03_24") (pintype "bidirectional"))
    )
    (net (code "90") (name "unconnected-(IC1-PB04-Pad22)") (class "Default")
      (node (ref "IC1") (pin "22") (pinfunction "PB04_22") (pintype "bidirectional"))
    )
    (net (code "91") (name "unconnected-(IC1-PB05-Pad121)") (class "Default")
      (node (ref "IC1") (pin "121") (pinfunction "PB05_121") (pintype "bidirectional"))
    )
    (net (code "92") (name "unconnected-(IC1-PB06-Pad134)") (class "Default")
      (node (ref "IC1") (pin "134") (pinfunction "PB06_134") (pintype "bidirectional"))
    )
    (net (code "93") (name "unconnected-(IC1-PB07-Pad135)") (class "Default")
      (node (ref "IC1") (pin "135") (pinfunction "PB07_135") (pintype "bidirectional"))
    )
    (net (code "94") (name "unconnected-(IC1-PB08-Pad11)") (class "Default")
      (node (ref "IC1") (pin "11") (pinfunction "PB08_11") (pintype "bidirectional"))
    )
    (net (code "95") (name "unconnected-(IC1-PB09-Pad17)") (class "Default")
      (node (ref "IC1") (pin "17") (pinfunction "PB09_17") (pintype "bidirectional"))
    )
    (net (code "96") (name "unconnected-(IC1-PB11-Pad31)") (class "Default")
      (node (ref "IC1") (pin "31") (pinfunction "PB11_31") (pintype "bidirectional"))
    )
    (net (code "97") (name "unconnected-(IC1-PC00-Pad98)") (class "Default")
      (node (ref "IC1") (pin "98") (pinfunction "PC00_98") (pintype "bidirectional"))
    )
    (net (code "98") (name "unconnected-(IC1-PC01-Pad99)") (class "Default")
      (node (ref "IC1") (pin "99") (pinfunction "PC01_99") (pintype "bidirectional"))
    )
    (net (code "99") (name "unconnected-(IC1-PC05-Pad12)") (class "Default")
      (node (ref "IC1") (pin "12") (pinfunction "PC05_12") (pintype "bidirectional"))
    )
    (net (code "100") (name "unconnected-(IC1-PX00-Pad55)") (class "Default")
      (node (ref "IC1") (pin "55") (pinfunction "PX00_55") (pintype "bidirectional"))
    )
    (net (code "101") (name "unconnected-(IC1-PX01-Pad59)") (class "Default")
      (node (ref "IC1") (pin "59") (pinfunction "PX01_59") (pintype "bidirectional"))
    )
    (net (code "102") (name "unconnected-(IC1-PX02-Pad62)") (class "Default")
      (node (ref "IC1") (pin "62") (pinfunction "PX02_62") (pintype "bidirectional"))
    )
    (net (code "103") (name "unconnected-(IC1-PX03-Pad63)") (class "Default")
      (node (ref "IC1") (pin "63") (pinfunction "PX03_63") (pintype "bidirectional"))
    )
    (net (code "104") (name "unconnected-(IC1-PX06-Pad53)") (class "Default")
      (node (ref "IC1") (pin "53") (pinfunction "PX06_53") (pintype "bidirectional"))
    )
    (net (code "105") (name "unconnected-(IC1-PX07-Pad54)") (class "Default")
      (node (ref "IC1") (pin "54") (pinfunction "PX07_54") (pintype "bidirectional"))
    )
    (net (code "106") (name "unconnected-(IC1-PX08-Pad50)") (class "Default")
      (node (ref "IC1") (pin "50") (pinfunction "PX08_50") (pintype "bidirectional"))
    )
    (net (code "107") (name "unconnected-(IC1-PX09-Pad49)") (class "Default")
      (node (ref "IC1") (pin "49") (pinfunction "PX09_49") (pintype "bidirectional"))
    )
    (net (code "108") (name "unconnected-(IC1-PX10-Pad37)") (class "Default")
      (node (ref "IC1") (pin "37") (pinfunction "PX10_37") (pintype "bidirectional"))
    )
    (net (code "109") (name "unconnected-(IC1-PX11-Pad67)") (class "Default")
      (node (ref "IC1") (pin "67") (pinfunction "PX11_67") (pintype "bidirectional"))
    )
    (net (code "110") (name "unconnected-(IC1-PX12-Pad34)") (class "Default")
      (node (ref "IC1") (pin "34") (pinfunction "PX12_34") (pintype "bidirectional"))
    )
    (net (code "111") (name "unconnected-(IC1-PX13-Pad33)") (class "Default")
      (node (ref "IC1") (pin "33") (pinfunction "PX13_33") (pintype "bidirectional"))
    )
    (net (code "112") (name "unconnected-(IC1-PX14-Pad68)") (class "Default")
      (node (ref "IC1") (pin "68") (pinfunction "PX14_68") (pintype "bidirectional"))
    )
    (net (code "113") (name "unconnected-(IC1-PX15-Pad40)") (class "Default")
      (node (ref "IC1") (pin "40") (pinfunction "PX15_40") (pintype "bidirectional"))
    )
    (net (code "114") (name "unconnected-(IC1-PX17-Pad83)") (class "Default")
      (node (ref "IC1") (pin "83") (pinfunction "PX17_83") (pintype "bidirectional"))
    )
    (net (code "115") (name "unconnected-(IC1-PX18-Pad84)") (class "Default")
      (node (ref "IC1") (pin "84") (pinfunction "PX18_84") (pintype "bidirectional"))
    )
    (net (code "116") (name "unconnected-(IC1-PX19-Pad35)") (class "Default")
      (node (ref "IC1") (pin "35") (pinfunction "PX19_35") (pintype "bidirectional"))
    )
    (net (code "117") (name "unconnected-(IC1-PX21-Pad80)") (class "Default")
      (node (ref "IC1") (pin "80") (pinfunction "PX21_80") (pintype "bidirectional"))
    )
    (net (code "118") (name "unconnected-(IC1-PX22-Pad72)") (class "Default")
      (node (ref "IC1") (pin "72") (pinfunction "PX22_72") (pintype "bidirectional"))
    )
    (net (code "119") (name "unconnected-(IC1-PX25-Pad92)") (class "Default")
      (node (ref "IC1") (pin "92") (pinfunction "PX25_92") (pintype "bidirectional"))
    )
    (net (code "120") (name "unconnected-(IC1-PX30-Pad96)") (class "Default")
      (node (ref "IC1") (pin "96") (pinfunction "PX30_96") (pintype "bidirectional"))
    )
    (net (code "121") (name "unconnected-(IC1-PX31-Pad97)") (class "Default")
      (node (ref "IC1") (pin "97") (pinfunction "PX31_97") (pintype "bidirectional"))
    )
    (net (code "122") (name "unconnected-(IC1-PX33-Pad95)") (class "Default")
      (node (ref "IC1") (pin "95") (pinfunction "PX33_95") (pintype "bidirectional"))
    )
    (net (code "123") (name "unconnected-(IC1-PX37-Pad45)") (class "Default")
      (node (ref "IC1") (pin "45") (pinfunction "PX37_45") (pintype "bidirectional"))
    )
    (net (code "124") (name "unconnected-(IC1-PX38-Pad51)") (class "Default")
      (node (ref "IC1") (pin "51") (pinfunction "PX38_51") (pintype "bidirectional"))
    )
    (net (code "125") (name "unconnected-(IC1-PX39-Pad52)") (class "Default")
      (node (ref "IC1") (pin "52") (pinfunction "PX39_52") (pintype "bidirectional"))
    )
    (net (code "126") (name "unconnected-(IC1-PX40-Pad36)") (class "Default")
      (node (ref "IC1") (pin "36") (pinfunction "PX40_36") (pintype "bidirectional"))
    )
    (net (code "127") (name "unconnected-(IC1-PX41-Pad71)") (class "Default")
      (node (ref "IC1") (pin "71") (pinfunction "PX41_71") (pintype "bidirectional"))
    )
    (net (code "128") (name "unconnected-(IC1-PX42-Pad69)") (class "Default")
      (node (ref "IC1") (pin "69") (pinfunction "PX42_69") (pintype "bidirectional"))
    )
    (net (code "129") (name "unconnected-(IC1-PX43-Pad88)") (class "Default")
      (node (ref "IC1") (pin "88") (pinfunction "PX43_88") (pintype "bidirectional"))
    )
    (net (code "130") (name "unconnected-(IC1-PX44-Pad66)") (class "Default")
      (node (ref "IC1") (pin "66") (pinfunction "PX44_66") (pintype "bidirectional"))
    )
    (net (code "131") (name "unconnected-(IC1-PX45-Pad70)") (class "Default")
      (node (ref "IC1") (pin "70") (pinfunction "PX45_70") (pintype "bidirectional"))
    )
    (net (code "132") (name "unconnected-(IC1-PX47-Pad39)") (class "Default")
      (node (ref "IC1") (pin "39") (pinfunction "PX47_39") (pintype "bidirectional"))
    )
    (net (code "133") (name "unconnected-(IC1-PX48-Pad41)") (class "Default")
      (node (ref "IC1") (pin "41") (pinfunction "PX48_41") (pintype "bidirectional"))
    )
    (net (code "134") (name "unconnected-(IC1-PX49-Pad43)") (class "Default")
      (node (ref "IC1") (pin "43") (pinfunction "PX49_43") (pintype "bidirectional"))
    )
    (net (code "135") (name "unconnected-(IC1-PX50-Pad75)") (class "Default")
      (node (ref "IC1") (pin "75") (pinfunction "PX50_75") (pintype "bidirectional"))
    )
    (net (code "136") (name "unconnected-(IC1-PX51-Pad77)") (class "Default")
      (node (ref "IC1") (pin "77") (pinfunction "PX51_77") (pintype "bidirectional"))
    )
    (net (code "137") (name "unconnected-(IC1-PX52-Pad87)") (class "Default")
      (node (ref "IC1") (pin "87") (pinfunction "PX52_87") (pintype "bidirectional"))
    )
    (net (code "138") (name "unconnected-(IC1-PX53-Pad42)") (class "Default")
      (node (ref "IC1") (pin "42") (pinfunction "PX53_42") (pintype "bidirectional"))
    )
    (net (code "139") (name "unconnected-(IC1-PX54-Pad46)") (class "Default")
      (node (ref "IC1") (pin "46") (pinfunction "PX54_46") (pintype "bidirectional"))
    )
    (net (code "140") (name "unconnected-(IC1-PX55-Pad79)") (class "Default")
      (node (ref "IC1") (pin "79") (pinfunction "PX55_79") (pintype "bidirectional"))
    )
    (net (code "141") (name "unconnected-(IC1-PX56-Pad78)") (class "Default")
      (node (ref "IC1") (pin "78") (pinfunction "PX56_78") (pintype "bidirectional"))
    )
    (net (code "142") (name "unconnected-(IC1-PX57-Pad76)") (class "Default")
      (node (ref "IC1") (pin "76") (pinfunction "PX57_76") (pintype "bidirectional"))
    )
    (net (code "143") (name "unconnected-(IC1-PX58-Pad57)") (class "Default")
      (node (ref "IC1") (pin "57") (pinfunction "PX58_57") (pintype "bidirectional"))
    )
    (net (code "144") (name "unconnected-(IC1-PX59-Pad56)") (class "Default")
      (node (ref "IC1") (pin "56") (pinfunction "PX59_56") (pintype "bidirectional"))
    )
    (net (code "145") (name "unconnected-(IC4-EN-Pad10)") (class "Default")
      (node (ref "IC4") (pin "10") (pinfunction "EN_10") (pintype "input"))
    )
    (net (code "146") (name "unconnected-(IC4-NC-Pad7)") (class "Default")
      (node (ref "IC4") (pin "7") (pinfunction "NC_7") (pintype "no_connect"))
    )
    (net (code "147") (name "unconnected-(SV2-Pad7)") (class "Default")
      (node (ref "SV2") (pin "7") (pinfunction "7_7") (pintype "passive"))
    )
    (net (code "148") (name "unconnected-(SV2-Pad8)") (class "Default")
      (node (ref "SV2") (pin "8") (pinfunction "8_8") (pintype "passive"))
    )
  )
)
